# Buck-Boost-5V.net
KiCad netlist of a schematic drawn in Altium Designer
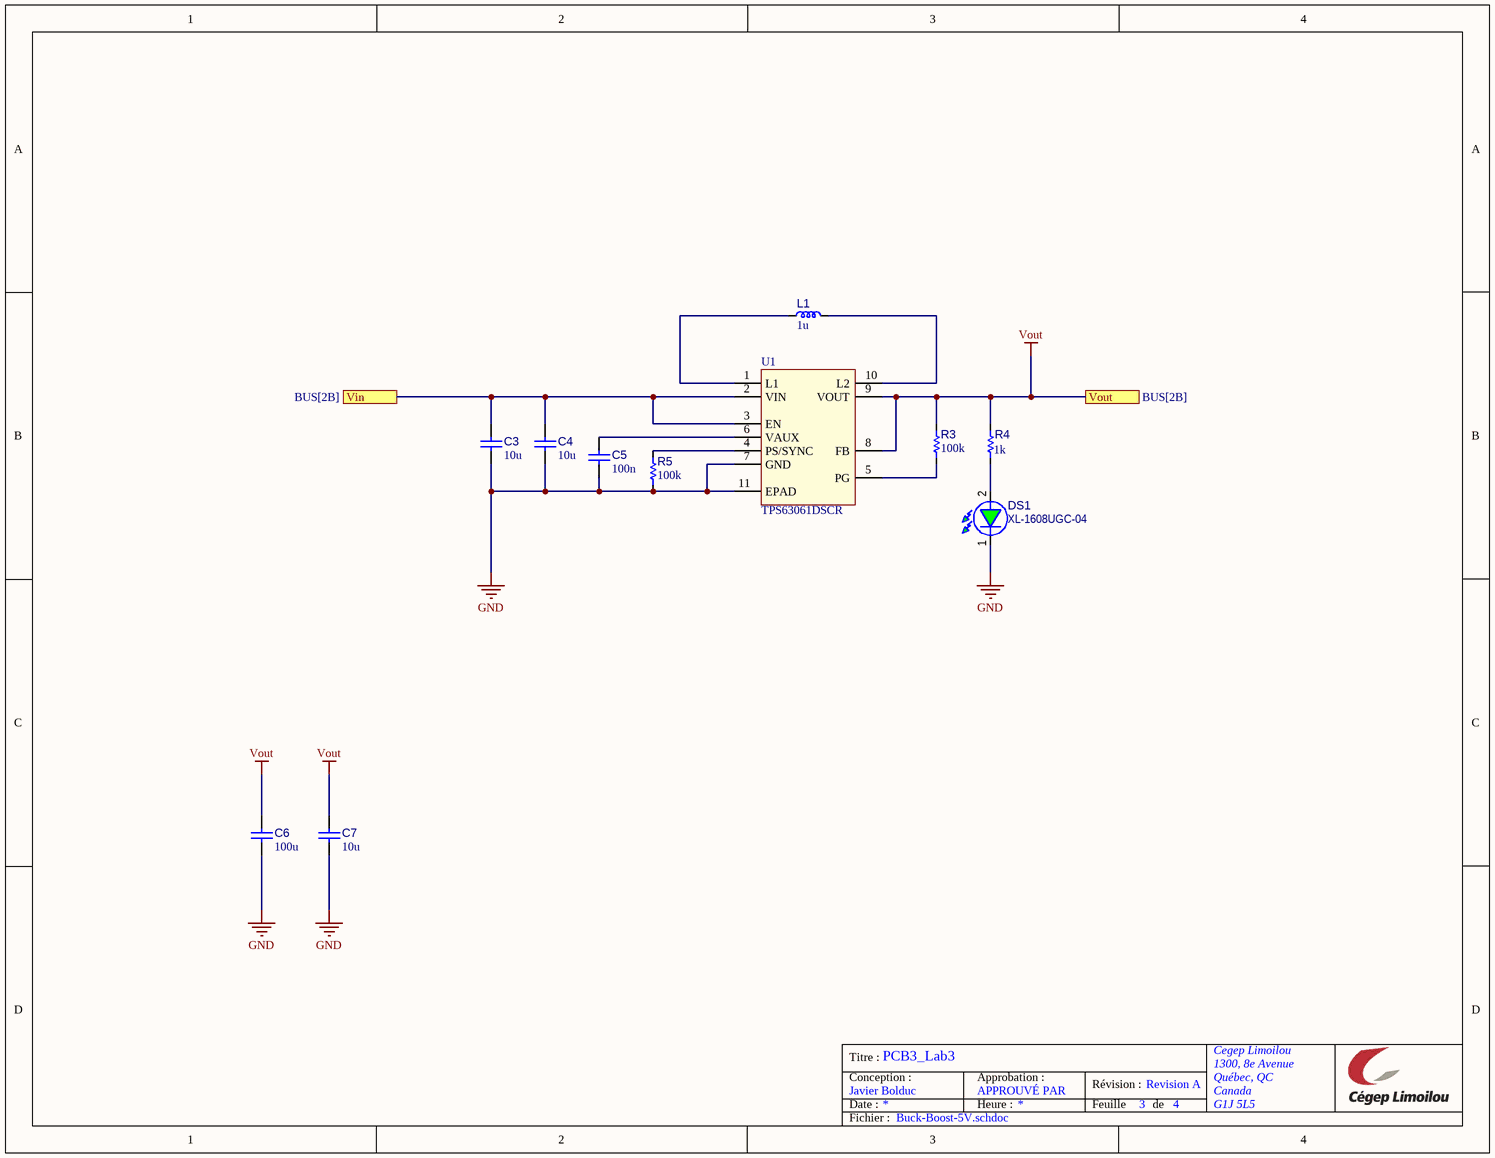
[diagram p0: Buck-Boost-5V.schdoc]

(export (version "E")
  (design (tool "Eeschema 10.0.6"))
  (components
    (comp (ref "C3")
      (value "10u")
      (footprint "C_2012[0805]")
      (description "Capacitor type 1")
      (fields (field (name "Comment") "CAP CER 10uF 10V X?? 0805"))
      (libsource (lib "TEP-AltiumLib-Passives-RLC") (part "capacitor"))
    )
    (comp (ref "C4")
      (value "10u")
      (footprint "C_2012[0805]")
      (description "Capacitor type 1")
      (fields (field (name "Comment") "CAP CER 10uF 10V X?? 0805"))
      (libsource (lib "TEP-AltiumLib-Passives-RLC") (part "capacitor"))
    )
    (comp (ref "C5")
      (value "100n")
      (footprint "C_1608[0603]")
      (description "Capacitor type 1")
      (fields (field (name "TOLERANCE") "10%") (field (name "Comment") "CAP CER 100nF 50V 0603"))
      (libsource (lib "TEP-AltiumLib-Passives-RLC") (part "capacitor"))
    )
    (comp (ref "C6")
      (value "100u")
      (footprint "C_3216[1206]")
      (description "Capacitor type 1")
      (fields (field (name "TOLERANCE") "20%") (field (name "Comment") "CAP CER 100uF 10V 1206"))
      (libsource (lib "TEP-AltiumLib-Passives-RLC") (part "capacitor"))
    )
    (comp (ref "C7")
      (value "10u")
      (footprint "C_2012[0805]")
      (description "Capacitor type 1")
      (fields (field (name "Comment") "CAP CER 10uF 10V X?? 0805"))
      (libsource (lib "TEP-AltiumLib-Passives-RLC") (part "capacitor"))
    )
    (comp (ref "DS1")
      (value "XL-1608UGC-04")
      (footprint "D_LED_0603")
      (description "LED Green Clear 40mcd 140deg")
      (libsource (lib "TEP-AltiumLib-Discretes") (part "D_LED_GREEN_0603"))
    )
    (comp (ref "L1")
      (value "1u")
      (footprint "L_3030[1212]")
      (description "Inductor type 1")
      (fields (field (name "TOLERANCE") "25%") (field (name "Comment") "Inductor 1UH 1.6A 51mΩ SMD"))
      (libsource (lib "TEP-AltiumLib-Passives-RLC") (part "inductor"))
    )
    (comp (ref "R3")
      (value "100k")
      (footprint "R_1608[0603]")
      (description "Resistor type 1")
      (fields (field (name "TOLERANCE") "1%") (field (name "Comment") "Res 100k 1% 0603"))
      (libsource (lib "TEP-AltiumLib-Passives-RLC") (part "resistor"))
    )
    (comp (ref "R4")
      (value "1k")
      (footprint "R_1608[0603]")
      (description "Resistor type 1")
      (fields (field (name "TOLERANCE") "1%") (field (name "Comment") "Res 1k 1% 0603"))
      (libsource (lib "TEP-AltiumLib-Passives-RLC") (part "resistor"))
    )
    (comp (ref "R5")
      (value "100k")
      (footprint "R_1608[0603]")
      (description "Resistor type 1")
      (fields (field (name "TOLERANCE") "1%") (field (name "Comment") "Res 100k 1% 0603"))
      (libsource (lib "TEP-AltiumLib-Passives-RLC") (part "resistor"))
    )
    (comp (ref "U1")
      (value "TPS63061DSCR")
      (footprint "U_WSON50P300X300X80-10N")
      (description "IC REG BUCK BOOST 5V 2A 10WSON")
      (libsource (lib "TEP-AltiumLib-ICs") (part "U_TPS63061DSC"))
    )
  )
  (nets
    (net (code "1") (name "/Vin") (class "Default")
      (node (ref "C3") (pin "1") (pinfunction "1_1") (pintype "passive"))
      (node (ref "C4") (pin "1") (pinfunction "1_1") (pintype "passive"))
      (node (ref "U1") (pin "2") (pinfunction "VIN_2") (pintype "passive"))
      (node (ref "U1") (pin "3") (pinfunction "EN_3") (pintype "passive"))
    )
    (net (code "2") (name "GND") (class "Default")
      (node (ref "C3") (pin "2") (pinfunction "2_2") (pintype "passive"))
      (node (ref "C4") (pin "2") (pinfunction "2_2") (pintype "passive"))
      (node (ref "C5") (pin "2") (pinfunction "2_2") (pintype "passive"))
      (node (ref "C6") (pin "2") (pinfunction "2_2") (pintype "passive"))
      (node (ref "C7") (pin "2") (pinfunction "2_2") (pintype "passive"))
      (node (ref "DS1") (pin "1") (pinfunction "K_1") (pintype "passive"))
      (node (ref "R5") (pin "2") (pinfunction "2_2") (pintype "passive"))
      (node (ref "U1") (pin "11") (pinfunction "EPAD_11") (pintype "passive"))
      (node (ref "U1") (pin "7") (pinfunction "GND_7") (pintype "passive"))
    )
    (net (code "3") (name "Net-(DS1-A)") (class "Default")
      (node (ref "DS1") (pin "2") (pinfunction "A_2") (pintype "passive"))
      (node (ref "R4") (pin "2") (pinfunction "2_2") (pintype "passive"))
    )
    (net (code "4") (name "Net-(U1-L1)") (class "Default")
      (node (ref "L1") (pin "1") (pinfunction "1_1") (pintype "passive"))
      (node (ref "U1") (pin "1") (pinfunction "L1_1") (pintype "passive"))
    )
    (net (code "5") (name "Net-(U1-L2)") (class "Default")
      (node (ref "L1") (pin "2") (pinfunction "2_2") (pintype "passive"))
      (node (ref "U1") (pin "10") (pinfunction "L2_10") (pintype "passive"))
    )
    (net (code "6") (name "Net-(U1-PG)") (class "Default")
      (node (ref "R3") (pin "2") (pinfunction "2_2") (pintype "passive"))
      (node (ref "U1") (pin "5") (pinfunction "PG_5") (pintype "passive"))
    )
    (net (code "7") (name "Net-(U1-PS{slash}SYNC)") (class "Default")
      (node (ref "R5") (pin "1") (pinfunction "1_1") (pintype "passive"))
      (node (ref "U1") (pin "4") (pinfunction "PS/SYNC_4") (pintype "passive"))
    )
    (net (code "8") (name "Net-(U1-VAUX)") (class "Default")
      (node (ref "C5") (pin "1") (pinfunction "1_1") (pintype "passive"))
      (node (ref "U1") (pin "6") (pinfunction "VAUX_6") (pintype "passive"))
    )
    (net (code "9") (name "Vout") (class "Default")
      (node (ref "C6") (pin "1") (pinfunction "1_1") (pintype "passive"))
      (node (ref "C7") (pin "1") (pinfunction "1_1") (pintype "passive"))
      (node (ref "R3") (pin "1") (pinfunction "1_1") (pintype "passive"))
      (node (ref "R4") (pin "1") (pinfunction "1_1") (pintype "passive"))
      (node (ref "U1") (pin "8") (pinfunction "FB_8") (pintype "passive"))
      (node (ref "U1") (pin "9") (pinfunction "VOUT_9") (pintype "passive"))
    )
  )
)
